# input.net
KiCad netlist of a schematic drawn in Altium Designer
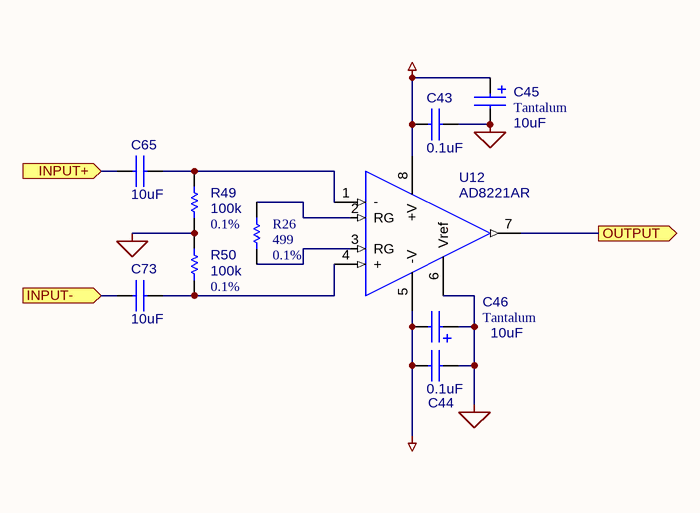
[diagram p0: input.SCHDOC]

(export (version "E")
  (design (tool "Eeschema 10.0.6"))
  (components
    (comp (ref "C43")
      (value "0.1uF")
      (footprint "0603")
      (description "Standard Capacitor")
      (fields (field (name "Comment") "CAPACITOR"))
      (libsource (lib "parts") (part "CAPACITOR"))
    )
    (comp (ref "C44")
      (value "0.1uF")
      (footprint "0603")
      (description "Standard Capacitor")
      (fields (field (name "Comment") "CAPACITOR"))
      (libsource (lib "parts") (part "CAPACITOR"))
    )
    (comp (ref "C45")
      (value "10uF")
      (footprint "3216")
      (description "Standard Capacitor")
      (fields (field (name "TYPE") "Tantalum") (field (name "Comment") "Tantalum"))
      (libsource (lib "parts") (part "POLCAP"))
    )
    (comp (ref "C46")
      (value "10uF")
      (footprint "3216")
      (description "Standard Capacitor")
      (fields (field (name "TYPE") "Tantalum") (field (name "Comment") "Tantalum"))
      (libsource (lib "parts") (part "POLCAP"))
    )
    (comp (ref "C65")
      (value "10uF")
      (footprint "0805")
      (description "Standard Capacitor")
      (fields (field (name "Comment") "CAPACITOR"))
      (libsource (lib "parts") (part "CAPACITOR"))
    )
    (comp (ref "C73")
      (value "10uF")
      (footprint "0805")
      (description "Standard Capacitor")
      (fields (field (name "Comment") "CAPACITOR"))
      (libsource (lib "parts") (part "CAPACITOR"))
    )
    (comp (ref "R26")
      (value "499")
      (footprint "0603")
      (description "Standard Passive Resistor")
      (fields (field (name "TOLERANCE") "0.1%"))
      (libsource (lib "parts") (part "RESISTOR"))
    )
    (comp (ref "R49")
      (value "100k")
      (footprint "0603")
      (description "Standard Passive Resistor")
      (fields (field (name "TOLERANCE") "0.1%"))
      (libsource (lib "parts") (part "RESISTOR"))
    )
    (comp (ref "R50")
      (value "100k")
      (footprint "0603")
      (description "Standard Passive Resistor")
      (fields (field (name "TOLERANCE") "0.1%"))
      (libsource (lib "parts") (part "RESISTOR"))
    )
    (comp (ref "U12")
      (value "AD8221AR")
      (footprint "SO-G8")
      (description "AD8221 Precision Instrumentation Amplifier")
      (libsource (lib "parts") (part "AD8221"))
    )
  )
  (nets
    (net (code "1") (name "/INPUT+") (class "Default") (node (ref "C65") (pin "1") (pintype "passive")))
    (net (code "2") (name "/INPUT-") (class "Default") (node (ref "C73") (pin "1") (pintype "passive")))
    (net (code "3") (name "/OUTPUT") (class "Default")
      (node (ref "U12") (pin "7") (pinfunction "Vout_7") (pintype "output"))
    )
    (net (code "4") (name "AGND") (class "Default")
      (node (ref "C43") (pin "2") (pintype "passive"))
      (node (ref "C44") (pin "2") (pintype "passive"))
      (node (ref "C45") (pin "2") (pintype "passive"))
      (node (ref "C46") (pin "1") (pintype "passive"))
      (node (ref "R49") (pin "2") (pintype "passive"))
      (node (ref "R50") (pin "1") (pintype "passive"))
      (node (ref "U12") (pin "6") (pinfunction "Vref_6") (pintype "passive"))
    )
    (net (code "5") (name "AVDD") (class "Default")
      (node (ref "C43") (pin "1") (pintype "passive"))
      (node (ref "C45") (pin "1") (pintype "passive"))
      (node (ref "U12") (pin "8") (pinfunction "+V_8") (pintype "power_in"))
    )
    (net (code "6") (name "AVSS") (class "Default")
      (node (ref "C44") (pin "1") (pintype "passive"))
      (node (ref "C46") (pin "2") (pintype "passive"))
      (node (ref "U12") (pin "5") (pinfunction "-V_5") (pintype "power_in"))
    )
    (net (code "7") (name "Net-(R26-Pad1)") (class "Default")
      (node (ref "R26") (pin "1") (pintype "passive"))
      (node (ref "U12") (pin "2") (pinfunction "RG_2") (pintype "input"))
    )
    (net (code "8") (name "Net-(R26-Pad2)") (class "Default")
      (node (ref "R26") (pin "2") (pintype "passive"))
      (node (ref "U12") (pin "3") (pinfunction "RG_3") (pintype "input"))
    )
    (net (code "9") (name "Net-(U12-+)") (class "Default")
      (node (ref "C73") (pin "2") (pintype "passive"))
      (node (ref "R50") (pin "2") (pintype "passive"))
      (node (ref "U12") (pin "4") (pinfunction "+_4") (pintype "input"))
    )
    (net (code "10") (name "Net-(U12--)") (class "Default")
      (node (ref "C65") (pin "2") (pintype "passive"))
      (node (ref "R49") (pin "1") (pintype "passive"))
      (node (ref "U12") (pin "1") (pinfunction "-_1") (pintype "input"))
    )
  )
)
